# 1_01_MCU_SchDoc.net
KiCad netlist of a schematic drawn in Altium Designer
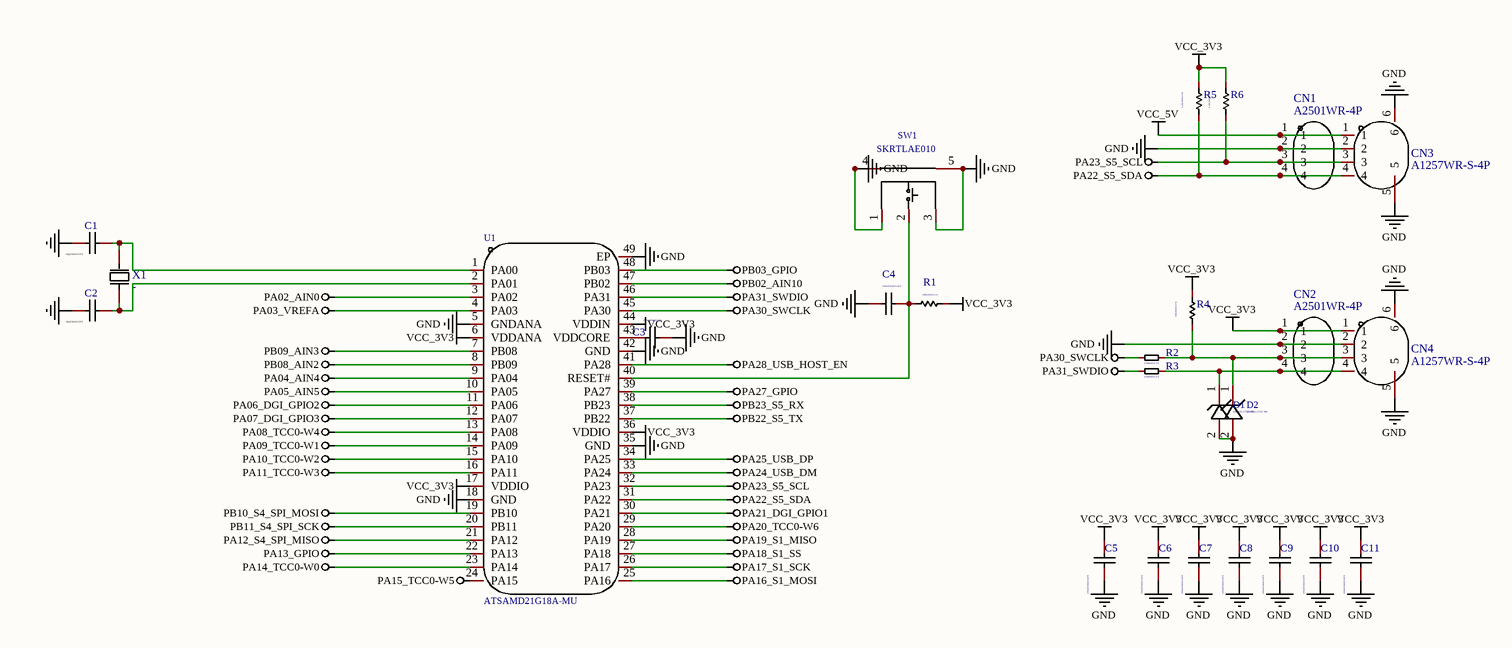
[diagram p0: 1_01 MCU.SchDoc.schdoc]

(export (version "E")
  (design (tool "Eeschema 10.0.6"))
  (components
    (comp (ref "C1")
      (value "18pF/0402/50V")
      (footprint "C0402")
      (fields (field (name "PUBLISHER") "Altium Limited"))
      (libsource (lib "altium-import") (part "root_2_18pF/0402/50V_"))
    )
    (comp (ref "C2")
      (value "18pF/0402/50V")
      (footprint "C0402")
      (fields (field (name "PUBLISHER") "Altium Limited"))
      (libsource (lib "altium-import") (part "root_2_18pF/0402/50V_"))
    )
    (comp (ref "C3")
      (value "100nF/0603/50V")
      (footprint "C0402")
      (fields (field (name "NAME") "100nF/0603/50V") (field (name "PUBLISHER") "Altium Limited"))
      (libsource (lib "altium-import") (part "root_0_100nF/0603/50V_"))
    )
    (comp (ref "C4")
      (value "100nF/0402/50V")
      (footprint "C0402")
      (fields (field (name "NAME") "100nF/0402/50V") (field (name "PUBLISHER") "Altium Limited"))
      (libsource (lib "altium-import") (part "root_0_100nF/0402/50V_"))
    )
    (comp (ref "C5")
      (value "100nF/0603/50V")
      (footprint "C0402")
      (fields (field (name "NAME") "100nF/0603/50V") (field (name "PUBLISHER") "Altium Limited"))
      (libsource (lib "altium-import") (part "root_3_100nF/0603/50V_"))
    )
    (comp (ref "C6")
      (value "100nF/0603/50V")
      (footprint "C0402")
      (fields (field (name "NAME") "100nF/0603/50V") (field (name "PUBLISHER") "Altium Limited"))
      (libsource (lib "altium-import") (part "root_3_100nF/0603/50V_"))
    )
    (comp (ref "C7")
      (value "100nF/0603/50V")
      (footprint "C0402")
      (fields (field (name "NAME") "100nF/0603/50V") (field (name "PUBLISHER") "Altium Limited"))
      (libsource (lib "altium-import") (part "root_3_100nF/0603/50V_"))
    )
    (comp (ref "C8")
      (value "100nF/0603/50V")
      (footprint "C0402")
      (fields (field (name "NAME") "100nF/0603/50V") (field (name "PUBLISHER") "Altium Limited"))
      (libsource (lib "altium-import") (part "root_3_100nF/0603/50V_"))
    )
    (comp (ref "C9")
      (value "100nF/0603/50V")
      (footprint "C0402")
      (fields (field (name "NAME") "100nF/0603/50V") (field (name "PUBLISHER") "Altium Limited"))
      (libsource (lib "altium-import") (part "root_3_100nF/0603/50V_"))
    )
    (comp (ref "C10")
      (value "100nF/0603/50V")
      (footprint "C0402")
      (fields (field (name "NAME") "100nF/0603/50V") (field (name "PUBLISHER") "Altium Limited"))
      (libsource (lib "altium-import") (part "root_3_100nF/0603/50V_"))
    )
    (comp (ref "C11")
      (value "100nF/0603/50V")
      (footprint "C0402")
      (fields (field (name "NAME") "100nF/0603/50V") (field (name "PUBLISHER") "Altium Limited"))
      (libsource (lib "altium-import") (part "root_3_100nF/0603/50V_"))
    )
    (comp (ref "CN1")
      (value "A2501WR-4P")
      (footprint "CONN-TH_A2501WR-4P")
      (fields (field (name "NAME") "A2501WR-4P") (field (name "MANUFACTURER") "CJT(长江连接器)"))
      (libsource (lib "altium-import") (part "root_0_A2501WR-4P_"))
    )
    (comp (ref "CN2")
      (value "A2501WR-4P")
      (footprint "CONN-TH_A2501WR-4P")
      (fields (field (name "NAME") "A2501WR-4P") (field (name "MANUFACTURER") "CJT(长江连接器)"))
      (libsource (lib "altium-import") (part "root_0_A2501WR-4P_"))
    )
    (comp (ref "CN3")
      (value "A1257WR-S-4P")
      (footprint "CONN-SMD_A1257WR-S-4P")
      (fields (field (name "NAME") "A1257WR-S-4P") (field (name "MANUFACTURER") "CJT(长江连接器)"))
      (libsource (lib "altium-import") (part "root_0_A1257WR-S-4P_"))
    )
    (comp (ref "CN4")
      (value "A1257WR-S-4P")
      (footprint "CONN-SMD_A1257WR-S-4P")
      (fields (field (name "NAME") "A1257WR-S-4P") (field (name "MANUFACTURER") "CJT(长江连接器)"))
      (libsource (lib "altium-import") (part "root_0_A1257WR-S-4P_"))
    )
    (comp (ref "D1")
      (value "ESD5Z3.3T1G-MS")
      (footprint "SOD-523")
      (fields
        (field (name "NAME") "ESD5Z3.3T1G-MS")
        (field (name "MANUFACTURER") "MDD（Microdiode Electronics）")
        (field (name "MANUFACTURER PART") "ESD5Z5V0")
      )
      (libsource (lib "altium-import") (part "root_3_ESD5Z3.3T1G-MS_"))
    )
    (comp (ref "D2")
      (value "ESD5Z3.3T1G-MS")
      (footprint "SOD-523")
      (fields
        (field (name "NAME") "ESD5Z3.3T1G-MS")
        (field (name "MANUFACTURER") "MDD（Microdiode Electronics）")
        (field (name "MANUFACTURER PART") "ESD5Z5V0")
      )
      (libsource (lib "altium-import") (part "root_3_ESD5Z3.3T1G-MS_"))
    )
    (comp (ref "R1")
      (value "10K/0402/1%")
      (footprint "R0402")
      (fields (field (name "NAME") "10K/0402/1%") (field (name "PUBLISHER") "Altium Limited"))
      (libsource (lib "altium-import") (part "root_0_10K/0402/1%_"))
    )
    (comp (ref "R2")
      (value "22R/0402/1%")
      (footprint "R0402")
      (fields (field (name "NAME") "22R/0402/1%"))
      (libsource (lib "altium-import") (part "root_0_22R/0402/1%_"))
    )
    (comp (ref "R3")
      (value "22R/0402/1%")
      (footprint "R0402")
      (fields (field (name "NAME") "22R/0402/1%"))
      (libsource (lib "altium-import") (part "root_0_22R/0402/1%_"))
    )
    (comp (ref "R4")
      (value "10K/0402/1%")
      (footprint "R0402")
      (fields (field (name "NAME") "10K/0402/1%") (field (name "PUBLISHER") "Altium Limited"))
      (libsource (lib "altium-import") (part "root_1_10K/0402/1%_"))
    )
    (comp (ref "R5")
      (value "2.2K/0402/1%")
      (footprint "R0402")
      (fields (field (name "NAME") "2.2K/0402/1%") (field (name "PUBLISHER") "Altium Limited"))
      (libsource (lib "altium-import") (part "root_1_2.2K/0402/1%_"))
    )
    (comp (ref "R6")
      (value "2.2K/0402/1%")
      (footprint "R0402")
      (fields (field (name "NAME") "2.2K/0402/1%") (field (name "PUBLISHER") "Altium Limited"))
      (libsource (lib "altium-import") (part "root_1_2.2K/0402/1%_"))
    )
    (comp (ref "SW1")
      (value "SKRTLAE010")
      (footprint "KEY-SMD_SKRTLAE010")
      (fields (field (name "NAME") "SKRTLAE010") (field (name "MANUFACTURER") "ALPS"))
      (libsource (lib "altium-import") (part "root_0_SKRTLAE010_"))
    )
    (comp (ref "U1")
      (value "ATSAMD21G18A-MU")
      (footprint "QFN-48_L7.0-W7.0-P0.50-TL-EP5.1")
      (fields (field (name "NAME") "ATSAMD21G18A-MU") (field (name "MANUFACTURER") "MICROCHIP(美国微芯)"))
      (libsource (lib "altium-import") (part "root_0_ATSAMD21G18A-MU_"))
    )
    (comp (ref "X1")
      (value "-")
      (footprint "OSC-SMD_L3.2-W1.5")
      (fields
        (field (name "NAME") "-")
        (field (name "MANUFACTURER") "KDS(大真空)")
        (field (name "MANUFACTURER PART") "DST310S 32.768KHz")
      )
      (libsource (lib "altium-import") (part "root_1_-_"))
    )
  )
  (nets
    (net (code "1") (name "GND") (class "Default")
      (node (ref "C1") (pin "2") (pinfunction "2_2") (pintype "passive"))
      (node (ref "C10") (pin "2") (pinfunction "2_2") (pintype "passive"))
      (node (ref "C11") (pin "2") (pinfunction "2_2") (pintype "passive"))
      (node (ref "C2") (pin "2") (pinfunction "2_2") (pintype "passive"))
      (node (ref "C3") (pin "2") (pinfunction "2_2") (pintype "passive"))
      (node (ref "C4") (pin "1") (pinfunction "1_1") (pintype "passive"))
      (node (ref "C5") (pin "2") (pinfunction "2_2") (pintype "passive"))
      (node (ref "C6") (pin "2") (pinfunction "2_2") (pintype "passive"))
      (node (ref "C7") (pin "2") (pinfunction "2_2") (pintype "passive"))
      (node (ref "C8") (pin "2") (pinfunction "2_2") (pintype "passive"))
      (node (ref "C9") (pin "2") (pinfunction "2_2") (pintype "passive"))
      (node (ref "CN1") (pin "2") (pinfunction "2_2") (pintype "passive"))
      (node (ref "CN2") (pin "2") (pinfunction "2_2") (pintype "passive"))
      (node (ref "CN3") (pin "2") (pinfunction "2_2") (pintype "passive"))
      (node (ref "CN3") (pin "5") (pinfunction "5_5") (pintype "passive"))
      (node (ref "CN3") (pin "6") (pinfunction "6_6") (pintype "passive"))
      (node (ref "CN4") (pin "2") (pinfunction "2_2") (pintype "passive"))
      (node (ref "CN4") (pin "5") (pinfunction "5_5") (pintype "passive"))
      (node (ref "CN4") (pin "6") (pinfunction "6_6") (pintype "passive"))
      (node (ref "D1") (pin "2") (pinfunction "A_2") (pintype "passive"))
      (node (ref "D2") (pin "2") (pinfunction "A_2") (pintype "passive"))
      (node (ref "SW1") (pin "1") (pinfunction "1_1") (pintype "passive"))
      (node (ref "SW1") (pin "3") (pinfunction "3_3") (pintype "passive"))
      (node (ref "SW1") (pin "4") (pinfunction "4_4") (pintype "passive"))
      (node (ref "SW1") (pin "5") (pinfunction "5_5") (pintype "passive"))
      (node (ref "U1") (pin "18") (pinfunction "GND_18") (pintype "passive"))
      (node (ref "U1") (pin "35") (pinfunction "GND_35") (pintype "passive"))
      (node (ref "U1") (pin "42") (pinfunction "GND_42") (pintype "passive"))
      (node (ref "U1") (pin "49") (pinfunction "EP_49") (pintype "passive"))
      (node (ref "U1") (pin "5") (pinfunction "GNDANA_5") (pintype "passive"))
    )
    (net (code "2") (name "Net-(D1-C)") (class "Default")
      (node (ref "CN2") (pin "4") (pinfunction "4_4") (pintype "passive"))
      (node (ref "CN4") (pin "4") (pinfunction "4_4") (pintype "passive"))
      (node (ref "D1") (pin "1") (pinfunction "C_1") (pintype "passive"))
      (node (ref "R3") (pin "2") (pinfunction "2_2") (pintype "passive"))
    )
    (net (code "3") (name "Net-(D2-C)") (class "Default")
      (node (ref "CN2") (pin "3") (pinfunction "3_3") (pintype "passive"))
      (node (ref "CN4") (pin "3") (pinfunction "3_3") (pintype "passive"))
      (node (ref "D2") (pin "1") (pinfunction "C_1") (pintype "passive"))
      (node (ref "R2") (pin "2") (pinfunction "2_2") (pintype "passive"))
      (node (ref "R4") (pin "1") (pinfunction "1_1") (pintype "passive"))
    )
    (net (code "4") (name "Net-(U1-PA00)") (class "Default")
      (node (ref "C1") (pin "1") (pinfunction "1_1") (pintype "passive"))
      (node (ref "U1") (pin "1") (pinfunction "PA00_1") (pintype "passive"))
      (node (ref "X1") (pin "2") (pinfunction "OSC2_2") (pintype "passive"))
    )
    (net (code "5") (name "Net-(U1-PA01)") (class "Default")
      (node (ref "C2") (pin "1") (pinfunction "1_1") (pintype "passive"))
      (node (ref "U1") (pin "2") (pinfunction "PA01_2") (pintype "passive"))
      (node (ref "X1") (pin "1") (pinfunction "OSC1_1") (pintype "passive"))
    )
    (net (code "6") (name "Net-(U1-RESET#)") (class "Default")
      (node (ref "C4") (pin "2") (pinfunction "2_2") (pintype "passive"))
      (node (ref "R1") (pin "1") (pinfunction "1_1") (pintype "passive"))
      (node (ref "SW1") (pin "2") (pinfunction "2_2") (pintype "passive"))
      (node (ref "U1") (pin "40") (pinfunction "RESET#_40") (pintype "passive"))
    )
    (net (code "7") (name "Net-(U1-VDDCORE)") (class "Default")
      (node (ref "C3") (pin "1") (pinfunction "1_1") (pintype "passive"))
      (node (ref "U1") (pin "43") (pinfunction "VDDCORE_43") (pintype "passive"))
    )
    (net (code "8") (name "PA02_AIN0") (class "Default")
      (node (ref "U1") (pin "3") (pinfunction "PA02_3") (pintype "passive"))
    )
    (net (code "9") (name "PA03_VREFA") (class "Default")
      (node (ref "U1") (pin "4") (pinfunction "PA03_4") (pintype "passive"))
    )
    (net (code "10") (name "PA04_AIN4") (class "Default")
      (node (ref "U1") (pin "9") (pinfunction "PA04_9") (pintype "passive"))
    )
    (net (code "11") (name "PA05_AIN5") (class "Default")
      (node (ref "U1") (pin "10") (pinfunction "PA05_10") (pintype "passive"))
    )
    (net (code "12") (name "PA06_DGI_GPIO2") (class "Default")
      (node (ref "U1") (pin "11") (pinfunction "PA06_11") (pintype "passive"))
    )
    (net (code "13") (name "PA07_DGI_GPIO3") (class "Default")
      (node (ref "U1") (pin "12") (pinfunction "PA07_12") (pintype "passive"))
    )
    (net (code "14") (name "PA08_TCC0-W4") (class "Default")
      (node (ref "U1") (pin "13") (pinfunction "PA08_13") (pintype "passive"))
    )
    (net (code "15") (name "PA09_TCC0-W1") (class "Default")
      (node (ref "U1") (pin "14") (pinfunction "PA09_14") (pintype "passive"))
    )
    (net (code "16") (name "PA10_TCC0-W2") (class "Default")
      (node (ref "U1") (pin "15") (pinfunction "PA10_15") (pintype "passive"))
    )
    (net (code "17") (name "PA11_TCC0-W3") (class "Default")
      (node (ref "U1") (pin "16") (pinfunction "PA11_16") (pintype "passive"))
    )
    (net (code "18") (name "PA12_S4_SPI_MISO") (class "Default")
      (node (ref "U1") (pin "21") (pinfunction "PA12_21") (pintype "passive"))
    )
    (net (code "19") (name "PA13_GPIO") (class "Default")
      (node (ref "U1") (pin "22") (pinfunction "PA13_22") (pintype "passive"))
    )
    (net (code "20") (name "PA14_TCC0-W0") (class "Default")
      (node (ref "U1") (pin "23") (pinfunction "PA14_23") (pintype "passive"))
    )
    (net (code "21") (name "PA15_TCC0-W5") (class "Default")
      (node (ref "U1") (pin "24") (pinfunction "PA15_24") (pintype "passive"))
    )
    (net (code "22") (name "PA16_S1_MOSI") (class "Default")
      (node (ref "U1") (pin "25") (pinfunction "PA16_25") (pintype "passive"))
    )
    (net (code "23") (name "PA17_S1_SCK") (class "Default")
      (node (ref "U1") (pin "26") (pinfunction "PA17_26") (pintype "passive"))
    )
    (net (code "24") (name "PA18_S1_SS") (class "Default")
      (node (ref "U1") (pin "27") (pinfunction "PA18_27") (pintype "passive"))
    )
    (net (code "25") (name "PA19_S1_MISO") (class "Default")
      (node (ref "U1") (pin "28") (pinfunction "PA19_28") (pintype "passive"))
    )
    (net (code "26") (name "PA20_TCC0-W6") (class "Default")
      (node (ref "U1") (pin "29") (pinfunction "PA20_29") (pintype "passive"))
    )
    (net (code "27") (name "PA21_DGI_GPIO1") (class "Default")
      (node (ref "U1") (pin "30") (pinfunction "PA21_30") (pintype "passive"))
    )
    (net (code "28") (name "PA22_S5_SDA") (class "Default")
      (node (ref "CN1") (pin "4") (pinfunction "4_4") (pintype "passive"))
      (node (ref "CN3") (pin "4") (pinfunction "4_4") (pintype "passive"))
      (node (ref "R5") (pin "1") (pinfunction "1_1") (pintype "passive"))
      (node (ref "U1") (pin "31") (pinfunction "PA22_31") (pintype "passive"))
    )
    (net (code "29") (name "PA23_S5_SCL") (class "Default")
      (node (ref "CN1") (pin "3") (pinfunction "3_3") (pintype "passive"))
      (node (ref "CN3") (pin "3") (pinfunction "3_3") (pintype "passive"))
      (node (ref "R6") (pin "1") (pinfunction "1_1") (pintype "passive"))
      (node (ref "U1") (pin "32") (pinfunction "PA23_32") (pintype "passive"))
    )
    (net (code "30") (name "PA24_USB_DM") (class "Default")
      (node (ref "U1") (pin "33") (pinfunction "PA24_33") (pintype "passive"))
    )
    (net (code "31") (name "PA25_USB_DP") (class "Default")
      (node (ref "U1") (pin "34") (pinfunction "PA25_34") (pintype "passive"))
    )
    (net (code "32") (name "PA27_GPIO") (class "Default")
      (node (ref "U1") (pin "39") (pinfunction "PA27_39") (pintype "passive"))
    )
    (net (code "33") (name "PA28_USB_HOST_EN") (class "Default")
      (node (ref "U1") (pin "41") (pinfunction "PA28_41") (pintype "passive"))
    )
    (net (code "34") (name "PA30_SWCLK") (class "Default")
      (node (ref "R2") (pin "1") (pinfunction "1_1") (pintype "passive"))
      (node (ref "U1") (pin "45") (pinfunction "PA30_45") (pintype "passive"))
    )
    (net (code "35") (name "PA31_SWDIO") (class "Default")
      (node (ref "R3") (pin "1") (pinfunction "1_1") (pintype "passive"))
      (node (ref "U1") (pin "46") (pinfunction "PA31_46") (pintype "passive"))
    )
    (net (code "36") (name "PB02_AIN10") (class "Default")
      (node (ref "U1") (pin "47") (pinfunction "PB02_47") (pintype "passive"))
    )
    (net (code "37") (name "PB03_GPIO") (class "Default")
      (node (ref "U1") (pin "48") (pinfunction "PB03_48") (pintype "passive"))
    )
    (net (code "38") (name "PB08_AIN2") (class "Default")
      (node (ref "U1") (pin "8") (pinfunction "PB09_8") (pintype "passive"))
    )
    (net (code "39") (name "PB09_AIN3") (class "Default")
      (node (ref "U1") (pin "7") (pinfunction "PB08_7") (pintype "passive"))
    )
    (net (code "40") (name "PB10_S4_SPI_MOSI") (class "Default")
      (node (ref "U1") (pin "19") (pinfunction "PB10_19") (pintype "passive"))
    )
    (net (code "41") (name "PB11_S4_SPI_SCK") (class "Default")
      (node (ref "U1") (pin "20") (pinfunction "PB11_20") (pintype "passive"))
    )
    (net (code "42") (name "PB22_S5_TX") (class "Default")
      (node (ref "U1") (pin "37") (pinfunction "PB22_37") (pintype "passive"))
    )
    (net (code "43") (name "PB23_S5_RX") (class "Default")
      (node (ref "U1") (pin "38") (pinfunction "PB23_38") (pintype "passive"))
    )
    (net (code "44") (name "VCC_3V3") (class "Default")
      (node (ref "C10") (pin "1") (pinfunction "1_1") (pintype "passive"))
      (node (ref "C11") (pin "1") (pinfunction "1_1") (pintype "passive"))
      (node (ref "C5") (pin "1") (pinfunction "1_1") (pintype "passive"))
      (node (ref "C6") (pin "1") (pinfunction "1_1") (pintype "passive"))
      (node (ref "C7") (pin "1") (pinfunction "1_1") (pintype "passive"))
      (node (ref "C8") (pin "1") (pinfunction "1_1") (pintype "passive"))
      (node (ref "C9") (pin "1") (pinfunction "1_1") (pintype "passive"))
      (node (ref "CN2") (pin "1") (pinfunction "1_1") (pintype "passive"))
      (node (ref "CN4") (pin "1") (pinfunction "1_1") (pintype "passive"))
      (node (ref "R1") (pin "2") (pinfunction "2_2") (pintype "passive"))
      (node (ref "R4") (pin "2") (pinfunction "2_2") (pintype "passive"))
      (node (ref "R5") (pin "2") (pinfunction "2_2") (pintype "passive"))
      (node (ref "R6") (pin "2") (pinfunction "2_2") (pintype "passive"))
      (node (ref "U1") (pin "17") (pinfunction "VDDIO_17") (pintype "passive"))
      (node (ref "U1") (pin "36") (pinfunction "VDDIO_36") (pintype "passive"))
      (node (ref "U1") (pin "44") (pinfunction "VDDIN_44") (pintype "passive"))
      (node (ref "U1") (pin "6") (pinfunction "VDDANA_6") (pintype "passive"))
    )
    (net (code "45") (name "VCC_5V") (class "Default")
      (node (ref "CN1") (pin "1") (pinfunction "1_1") (pintype "passive"))
      (node (ref "CN3") (pin "1") (pinfunction "1_1") (pintype "passive"))
    )
  )
)
